# Sheet1.net
KiCad netlist of a schematic drawn in Altium Designer
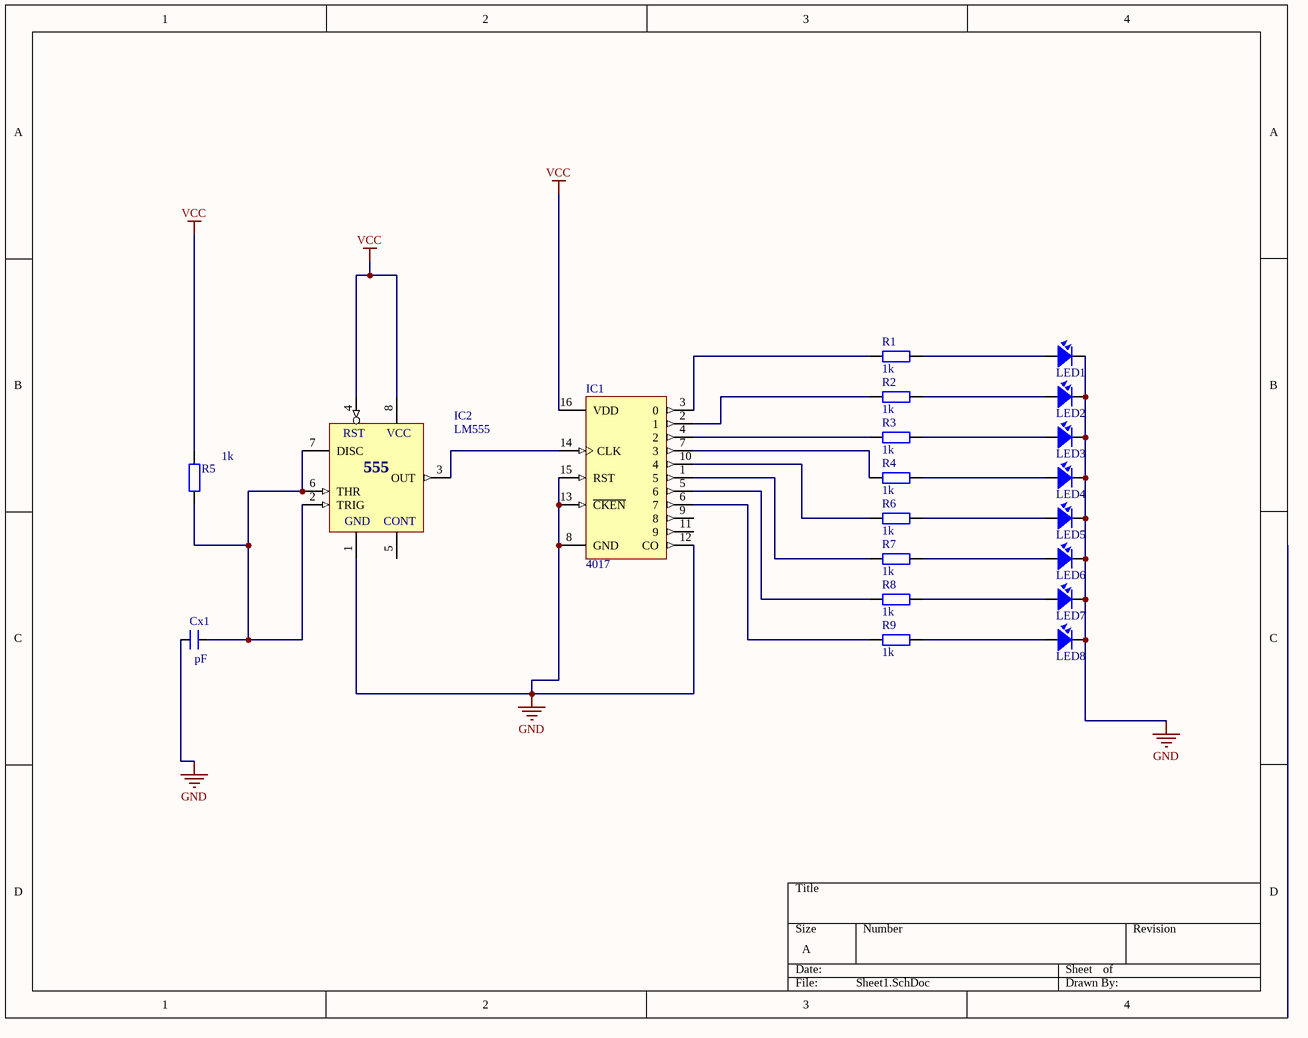
[diagram p0: Sheet1.SchDoc]

(export (version "E")
  (design (tool "Eeschema 10.0.6"))
  (components
    (comp (ref "Cx1")
      (value "pF")
      (footprint "CN1")
      (description "Cremic For Xtal 1pF => 100pF")
      (libsource (lib "syhaunguyen") (part "CN0"))
    )
    (comp (ref "IC1")
      (value "4017")
      (footprint "DIP16/W0.3")
      (description "Decade Counter/Divider with 10 Decoded Outputs")
      (fields (field (name "DESIGNED BY") "VanDungEvn"))
      (libsource (lib "syhaunguyen") (part "4017"))
    )
    (comp (ref "IC2")
      (value "LM555")
      (footprint "DIP8/W0.3")
      (description "Timer")
      (libsource (lib "syhaunguyen") (part "LM555"))
    )
    (comp (ref "LED1")
      (value "LED")
      (footprint "LED-3")
      (description "LED Single colour Green and Red")
      (libsource (lib "syhaunguyen") (part "LED"))
    )
    (comp (ref "LED2")
      (value "LED")
      (footprint "LED-3")
      (description "LED Single colour Green and Red")
      (libsource (lib "syhaunguyen") (part "LED"))
    )
    (comp (ref "LED3")
      (value "LED")
      (footprint "LED-3")
      (description "LED Single colour Green and Red")
      (libsource (lib "syhaunguyen") (part "LED"))
    )
    (comp (ref "LED4")
      (value "LED")
      (footprint "LED-3")
      (description "LED Single colour Green and Red")
      (libsource (lib "syhaunguyen") (part "LED"))
    )
    (comp (ref "LED5")
      (value "LED")
      (footprint "LED-3")
      (description "LED Single colour Green and Red")
      (libsource (lib "syhaunguyen") (part "LED"))
    )
    (comp (ref "LED6")
      (value "LED")
      (footprint "LED-3")
      (description "LED Single colour Green and Red")
      (libsource (lib "syhaunguyen") (part "LED"))
    )
    (comp (ref "LED7")
      (value "LED")
      (footprint "LED-3")
      (description "LED Single colour Green and Red")
      (libsource (lib "syhaunguyen") (part "LED"))
    )
    (comp (ref "LED8")
      (value "LED")
      (footprint "LED-3")
      (description "LED Single colour Green and Red")
      (libsource (lib "syhaunguyen") (part "LED"))
    )
    (comp (ref "R1")
      (value "1k")
      (footprint "R1/4W")
      (description "Resistor 1/4W")
      (libsource (lib "syhaunguyen") (part "R1/4W"))
    )
    (comp (ref "R2")
      (value "1k")
      (footprint "R1/4W")
      (description "Resistor 1/4W")
      (libsource (lib "syhaunguyen") (part "R1/4W"))
    )
    (comp (ref "R3")
      (value "1k")
      (footprint "R1/4W")
      (description "Resistor 1/4W")
      (libsource (lib "syhaunguyen") (part "R1/4W"))
    )
    (comp (ref "R4")
      (value "1k")
      (footprint "R1/4W")
      (description "Resistor 1/4W")
      (libsource (lib "syhaunguyen") (part "R1/4W"))
    )
    (comp (ref "R5")
      (value "1k")
      (footprint "R1/4W")
      (description "Resistor 1/4W")
      (libsource (lib "syhaunguyen") (part "R1/4W"))
    )
    (comp (ref "R6")
      (value "1k")
      (footprint "R1/4W")
      (description "Resistor 1/4W")
      (libsource (lib "syhaunguyen") (part "R1/4W"))
    )
    (comp (ref "R7")
      (value "1k")
      (footprint "R1/4W")
      (description "Resistor 1/4W")
      (libsource (lib "syhaunguyen") (part "R1/4W"))
    )
    (comp (ref "R8")
      (value "1k")
      (footprint "R1/4W")
      (description "Resistor 1/4W")
      (libsource (lib "syhaunguyen") (part "R1/4W"))
    )
    (comp (ref "R9")
      (value "1k")
      (footprint "R1/4W")
      (description "Resistor 1/4W")
      (libsource (lib "syhaunguyen") (part "R1/4W"))
    )
  )
  (nets
    (net (code "1") (name "GND") (class "Default")
      (node (ref "Cx1") (pin "1") (pinfunction "1_1") (pintype "passive"))
      (node (ref "IC1") (pin "12") (pinfunction "CO_12") (pintype "output"))
      (node (ref "IC1") (pin "13") (pinfunction "~{CKEN}_13") (pintype "input"))
      (node (ref "IC1") (pin "15") (pinfunction "RST_15") (pintype "input"))
      (node (ref "IC1") (pin "8") (pinfunction "GND_8") (pintype "power_in"))
      (node (ref "IC2") (pin "1") (pinfunction "GND_1") (pintype "power_in"))
      (node (ref "LED1") (pin "2") (pinfunction "2_2") (pintype "passive"))
      (node (ref "LED2") (pin "2") (pinfunction "2_2") (pintype "passive"))
      (node (ref "LED3") (pin "2") (pinfunction "2_2") (pintype "passive"))
      (node (ref "LED4") (pin "2") (pinfunction "2_2") (pintype "passive"))
      (node (ref "LED5") (pin "2") (pinfunction "2_2") (pintype "passive"))
      (node (ref "LED6") (pin "2") (pinfunction "2_2") (pintype "passive"))
      (node (ref "LED7") (pin "2") (pinfunction "2_2") (pintype "passive"))
      (node (ref "LED8") (pin "2") (pinfunction "2_2") (pintype "passive"))
    )
    (net (code "2") (name "Net-(IC1-0)") (class "Default")
      (node (ref "IC1") (pin "3") (pinfunction "0_3") (pintype "output"))
      (node (ref "R1") (pin "1") (pinfunction "1_1") (pintype "passive"))
    )
    (net (code "3") (name "Net-(IC1-1)") (class "Default")
      (node (ref "IC1") (pin "2") (pinfunction "1_2") (pintype "output"))
      (node (ref "R2") (pin "1") (pinfunction "1_1") (pintype "passive"))
    )
    (net (code "4") (name "Net-(IC1-2)") (class "Default")
      (node (ref "IC1") (pin "4") (pinfunction "2_4") (pintype "output"))
      (node (ref "R3") (pin "1") (pinfunction "1_1") (pintype "passive"))
    )
    (net (code "5") (name "Net-(IC1-3)") (class "Default")
      (node (ref "IC1") (pin "7") (pinfunction "3_7") (pintype "output"))
      (node (ref "R4") (pin "1") (pinfunction "1_1") (pintype "passive"))
    )
    (net (code "6") (name "Net-(IC1-4)") (class "Default")
      (node (ref "IC1") (pin "10") (pinfunction "4_10") (pintype "output"))
      (node (ref "R6") (pin "1") (pinfunction "1_1") (pintype "passive"))
    )
    (net (code "7") (name "Net-(IC1-5)") (class "Default")
      (node (ref "IC1") (pin "1") (pinfunction "5_1") (pintype "output"))
      (node (ref "R7") (pin "1") (pinfunction "1_1") (pintype "passive"))
    )
    (net (code "8") (name "Net-(IC1-6)") (class "Default")
      (node (ref "IC1") (pin "5") (pinfunction "6_5") (pintype "output"))
      (node (ref "R8") (pin "1") (pinfunction "1_1") (pintype "passive"))
    )
    (net (code "9") (name "Net-(IC1-7)") (class "Default")
      (node (ref "IC1") (pin "6") (pinfunction "7_6") (pintype "output"))
      (node (ref "R9") (pin "1") (pinfunction "1_1") (pintype "passive"))
    )
    (net (code "10") (name "Net-(IC1-CLK)") (class "Default")
      (node (ref "IC1") (pin "14") (pinfunction "CLK_14") (pintype "input"))
      (node (ref "IC2") (pin "3") (pinfunction "OUT_3") (pintype "output"))
    )
    (net (code "11") (name "Net-(IC2-DISC)") (class "Default")
      (node (ref "Cx1") (pin "2") (pinfunction "2_2") (pintype "passive"))
      (node (ref "IC2") (pin "2") (pinfunction "TRIG_2") (pintype "input"))
      (node (ref "IC2") (pin "6") (pinfunction "THR_6") (pintype "input"))
      (node (ref "IC2") (pin "7") (pinfunction "DISC_7") (pintype "open_collector"))
      (node (ref "R5") (pin "2") (pinfunction "2_2") (pintype "passive"))
    )
    (net (code "12") (name "Net-(LED1-Pad1)") (class "Default")
      (node (ref "LED1") (pin "1") (pinfunction "1_1") (pintype "passive"))
      (node (ref "R1") (pin "2") (pinfunction "2_2") (pintype "passive"))
    )
    (net (code "13") (name "Net-(LED2-Pad1)") (class "Default")
      (node (ref "LED2") (pin "1") (pinfunction "1_1") (pintype "passive"))
      (node (ref "R2") (pin "2") (pinfunction "2_2") (pintype "passive"))
    )
    (net (code "14") (name "Net-(LED3-Pad1)") (class "Default")
      (node (ref "LED3") (pin "1") (pinfunction "1_1") (pintype "passive"))
      (node (ref "R3") (pin "2") (pinfunction "2_2") (pintype "passive"))
    )
    (net (code "15") (name "Net-(LED4-Pad1)") (class "Default")
      (node (ref "LED4") (pin "1") (pinfunction "1_1") (pintype "passive"))
      (node (ref "R4") (pin "2") (pinfunction "2_2") (pintype "passive"))
    )
    (net (code "16") (name "Net-(LED5-Pad1)") (class "Default")
      (node (ref "LED5") (pin "1") (pinfunction "1_1") (pintype "passive"))
      (node (ref "R6") (pin "2") (pinfunction "2_2") (pintype "passive"))
    )
    (net (code "17") (name "Net-(LED6-Pad1)") (class "Default")
      (node (ref "LED6") (pin "1") (pinfunction "1_1") (pintype "passive"))
      (node (ref "R7") (pin "2") (pinfunction "2_2") (pintype "passive"))
    )
    (net (code "18") (name "Net-(LED7-Pad1)") (class "Default")
      (node (ref "LED7") (pin "1") (pinfunction "1_1") (pintype "passive"))
      (node (ref "R8") (pin "2") (pinfunction "2_2") (pintype "passive"))
    )
    (net (code "19") (name "Net-(LED8-Pad1)") (class "Default")
      (node (ref "LED8") (pin "1") (pinfunction "1_1") (pintype "passive"))
      (node (ref "R9") (pin "2") (pinfunction "2_2") (pintype "passive"))
    )
    (net (code "20") (name "VCC") (class "Default")
      (node (ref "IC1") (pin "16") (pinfunction "VDD_16") (pintype "power_in"))
      (node (ref "IC2") (pin "4") (pinfunction "RST_4") (pintype "input"))
      (node (ref "IC2") (pin "8") (pinfunction "VCC_8") (pintype "power_in"))
      (node (ref "R5") (pin "1") (pinfunction "1_1") (pintype "passive"))
    )
    (net (code "21") (name "unconnected-(IC1-8-Pad9)") (class "Default")
      (node (ref "IC1") (pin "9") (pinfunction "8_9") (pintype "output"))
    )
    (net (code "22") (name "unconnected-(IC1-9-Pad11)") (class "Default")
      (node (ref "IC1") (pin "11") (pinfunction "9_11") (pintype "output"))
    )
    (net (code "23") (name "unconnected-(IC2-CONT-Pad5)") (class "Default")
      (node (ref "IC2") (pin "5") (pinfunction "CONT_5") (pintype "passive"))
    )
  )
)
